# EmgFilterModule.net
KiCad netlist of a schematic drawn in Altium Designer
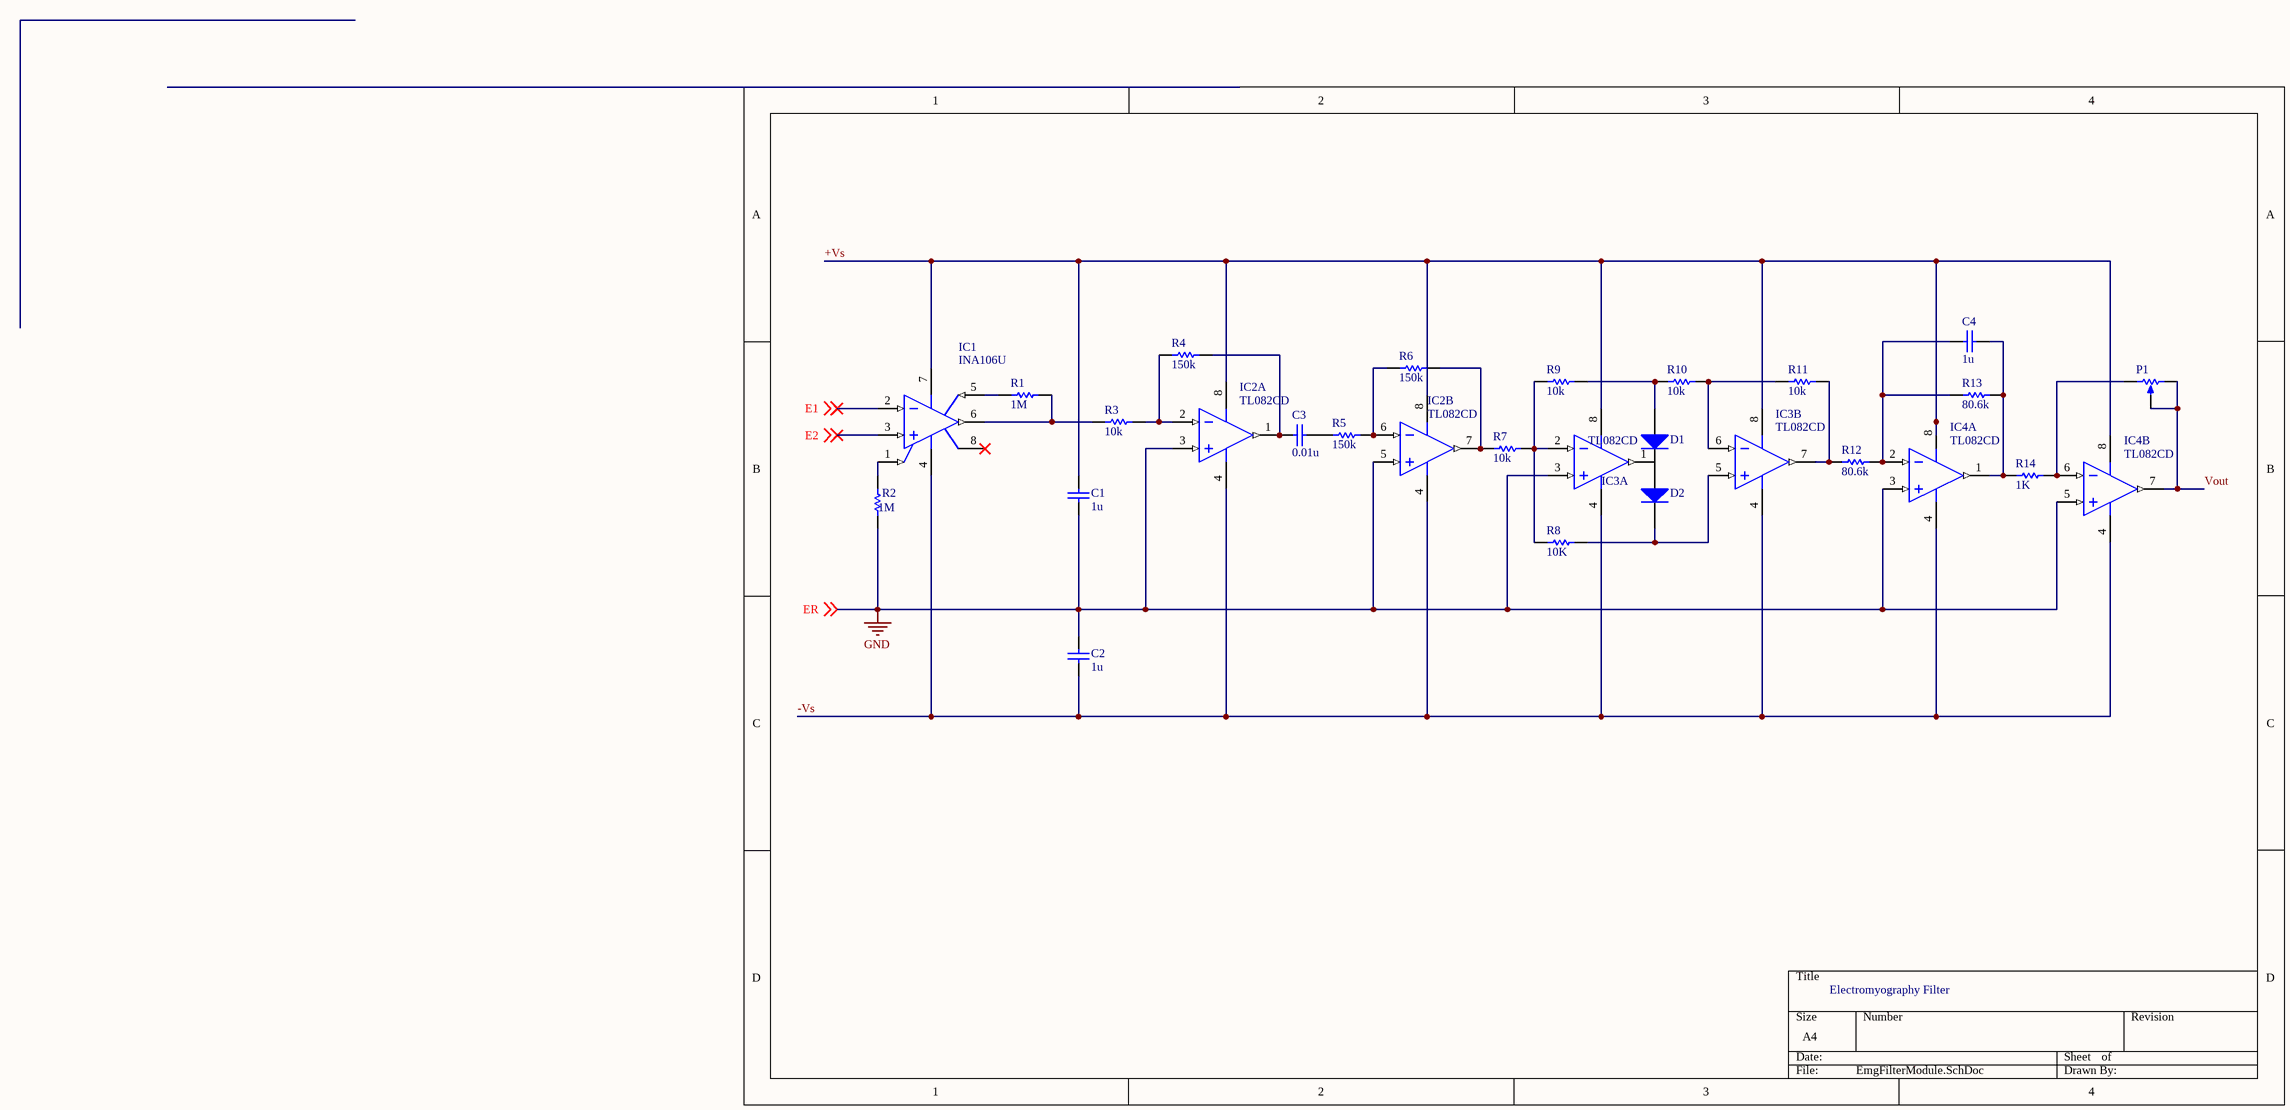
[diagram p0: EmgFilterModule.SchDoc]

(export (version "E")
  (design (tool "Eeschema 10.0.6"))
  (components
    (comp (ref "C1")
      (value "1u")
      (description "Capacitor")
      (libsource (lib "Simulation Generic Components") (part "Capacitor"))
    )
    (comp (ref "C2")
      (value "1u")
      (description "Capacitor")
      (libsource (lib "Simulation Generic Components") (part "Capacitor"))
    )
    (comp (ref "C3")
      (value "0.01u")
      (description "Capacitor")
      (libsource (lib "Simulation Generic Components") (part "Capacitor"))
    )
    (comp (ref "C4")
      (value "1u")
      (description "Capacitor")
      (libsource (lib "Simulation Generic Components") (part "Capacitor"))
    )
    (comp (ref "D1") (value "Diode") (libsource (lib "Simulation Generic Components") (part "Diode")))
    (comp (ref "D2") (value "Diode") (libsource (lib "Simulation Generic Components") (part "Diode")))
    (comp (ref "IC1")
      (value "INA106U")
      (footprint "D0008A_M")
      (fields (field (name "MANUFACTURER") "Texas Instruments"))
      (libsource (lib "Altium Content Vault") (part "TI-INA1XXXX8"))
    )
    (comp (ref "IC2")
      (value "TL082CD")
      (footprint "D0008A_L")
      (fields (field (name "MANUFACTURER") "Texas Instruments"))
      (libsource (lib "Altium Content Vault") (part "TI-AMP-D6-2-8_D"))
    )
    (comp (ref "IC3")
      (value "TL082CD")
      (footprint "D0008A_L")
      (fields (field (name "MANUFACTURER") "Texas Instruments"))
      (libsource (lib "Altium Content Vault") (part "TI-AMP-D6-2-8_D"))
    )
    (comp (ref "IC4")
      (value "TL082CD")
      (footprint "D0008A_L")
      (fields (field (name "MANUFACTURER") "Texas Instruments"))
      (libsource (lib "Altium Content Vault") (part "TI-AMP-D6-2-8_D"))
    )
    (comp (ref "P1")
      (value "Potentiometer")
      (libsource (lib "Simulation Generic Components") (part "Potentiometer"))
    )
    (comp (ref "R1")
      (value "1M")
      (description "Resistor")
      (libsource (lib "Simulation Generic Components") (part "Resistor"))
    )
    (comp (ref "R2")
      (value "1M")
      (description "Resistor")
      (libsource (lib "Simulation Generic Components") (part "Resistor"))
    )
    (comp (ref "R3")
      (value "10k")
      (description "Resistor")
      (libsource (lib "Simulation Generic Components") (part "Resistor"))
    )
    (comp (ref "R4")
      (value "150k")
      (description "Resistor")
      (libsource (lib "Simulation Generic Components") (part "Resistor"))
    )
    (comp (ref "R5")
      (value "150k")
      (description "Resistor")
      (libsource (lib "Simulation Generic Components") (part "Resistor"))
    )
    (comp (ref "R6")
      (value "150k")
      (description "Resistor")
      (libsource (lib "Simulation Generic Components") (part "Resistor"))
    )
    (comp (ref "R7")
      (value "10k")
      (description "Resistor")
      (libsource (lib "Simulation Generic Components") (part "Resistor"))
    )
    (comp (ref "R8")
      (value "10K")
      (description "Resistor")
      (libsource (lib "Simulation Generic Components") (part "Resistor"))
    )
    (comp (ref "R9")
      (value "10k")
      (description "Resistor")
      (libsource (lib "Simulation Generic Components") (part "Resistor"))
    )
    (comp (ref "R10")
      (value "10k")
      (description "Resistor")
      (libsource (lib "Simulation Generic Components") (part "Resistor"))
    )
    (comp (ref "R11")
      (value "10k")
      (description "Resistor")
      (libsource (lib "Simulation Generic Components") (part "Resistor"))
    )
    (comp (ref "R12")
      (value "80.6k")
      (description "Resistor")
      (libsource (lib "Simulation Generic Components") (part "Resistor"))
    )
    (comp (ref "R13")
      (value "80.6k")
      (description "Resistor")
      (libsource (lib "Simulation Generic Components") (part "Resistor"))
    )
    (comp (ref "R14")
      (value "1K")
      (description "Resistor")
      (libsource (lib "Simulation Generic Components") (part "Resistor"))
    )
  )
  (nets
    (net (code "1") (name "/+Vs") (class "Default")
      (node (ref "C1") (pin "2") (pinfunction "2_2") (pintype "passive"))
      (node (ref "IC1") (pin "7") (pinfunction "V+_7") (pintype "power_in"))
      (node (ref "IC2") (pin "8") (pinfunction "VCC+_8") (pintype "power_in"))
      (node (ref "IC3") (pin "8") (pinfunction "VCC+_8") (pintype "power_in"))
      (node (ref "IC4") (pin "8") (pinfunction "VCC+_8") (pintype "power_in"))
    )
    (net (code "2") (name "/-Vs") (class "Default")
      (node (ref "C2") (pin "1") (pinfunction "1_1") (pintype "passive"))
      (node (ref "IC1") (pin "4") (pinfunction "V-_4") (pintype "power_in"))
      (node (ref "IC2") (pin "4") (pinfunction "VCC-_4") (pintype "power_in"))
      (node (ref "IC3") (pin "4") (pinfunction "VCC-_4") (pintype "power_in"))
      (node (ref "IC4") (pin "4") (pinfunction "VCC-_4") (pintype "power_in"))
    )
    (net (code "3") (name "/Vout") (class "Default")
      (node (ref "IC4") (pin "7") (pinfunction "OUT2_7") (pintype "output"))
      (node (ref "P1") (pin "2") (pinfunction "BOT_2") (pintype "passive"))
      (node (ref "P1") (pin "3") (pinfunction "TAP_3") (pintype "passive"))
    )
    (net (code "4") (name "E1") (class "Default")
      (node (ref "IC1") (pin "2") (pinfunction "IN-_2") (pintype "input"))
    )
    (net (code "5") (name "E2") (class "Default")
      (node (ref "IC1") (pin "3") (pinfunction "IN+_3") (pintype "input"))
    )
    (net (code "6") (name "ER") (class "Default")
      (node (ref "C1") (pin "1") (pinfunction "1_1") (pintype "passive"))
      (node (ref "C2") (pin "2") (pinfunction "2_2") (pintype "passive"))
      (node (ref "IC2") (pin "3") (pinfunction "IN1+_3") (pintype "input"))
      (node (ref "IC2") (pin "5") (pinfunction "IN2+_5") (pintype "input"))
      (node (ref "IC3") (pin "3") (pinfunction "IN1+_3") (pintype "input"))
      (node (ref "IC4") (pin "3") (pinfunction "IN1+_3") (pintype "input"))
      (node (ref "IC4") (pin "5") (pinfunction "IN2+_5") (pintype "input"))
      (node (ref "R2") (pin "1") (pinfunction "1_1") (pintype "passive"))
    )
    (net (code "7") (name "Net-(C3-Pad2)") (class "Default")
      (node (ref "C3") (pin "2") (pinfunction "2_2") (pintype "passive"))
      (node (ref "R5") (pin "1") (pinfunction "1_1") (pintype "passive"))
    )
    (net (code "8") (name "Net-(D1-A)") (class "Default")
      (node (ref "D1") (pin "1") (pinfunction "A_1") (pintype "passive"))
      (node (ref "R10") (pin "1") (pinfunction "1_1") (pintype "passive"))
      (node (ref "R9") (pin "2") (pinfunction "2_2") (pintype "passive"))
    )
    (net (code "9") (name "Net-(D2-A)") (class "Default")
      (node (ref "D2") (pin "1") (pinfunction "A_1") (pintype "passive"))
      (node (ref "IC3") (pin "1") (pinfunction "OUT1_1") (pintype "output"))
    )
    (net (code "10") (name "Net-(D2-K)") (class "Default")
      (node (ref "D2") (pin "2") (pinfunction "K_2") (pintype "passive"))
      (node (ref "IC3") (pin "5") (pinfunction "IN2+_5") (pintype "input"))
      (node (ref "R8") (pin "2") (pinfunction "2_2") (pintype "passive"))
    )
    (net (code "11") (name "Net-(IC1-OUT)") (class "Default")
      (node (ref "IC1") (pin "6") (pinfunction "OUT_6") (pintype "output"))
      (node (ref "R1") (pin "2") (pinfunction "2_2") (pintype "passive"))
      (node (ref "R3") (pin "1") (pinfunction "1_1") (pintype "passive"))
    )
    (net (code "12") (name "Net-(IC1-REF)") (class "Default")
      (node (ref "IC1") (pin "1") (pinfunction "REF_1") (pintype "input"))
      (node (ref "R2") (pin "2") (pinfunction "2_2") (pintype "passive"))
    )
    (net (code "13") (name "Net-(IC1-SENSE)") (class "Default")
      (node (ref "IC1") (pin "5") (pinfunction "SENSE_5") (pintype "input"))
      (node (ref "R1") (pin "1") (pinfunction "1_1") (pintype "passive"))
    )
    (net (code "14") (name "Net-(IC2A-IN1-)") (class "Default")
      (node (ref "IC2") (pin "2") (pinfunction "IN1-_2") (pintype "input"))
      (node (ref "R3") (pin "2") (pinfunction "2_2") (pintype "passive"))
      (node (ref "R4") (pin "1") (pinfunction "1_1") (pintype "passive"))
    )
    (net (code "15") (name "Net-(IC2A-OUT1)") (class "Default")
      (node (ref "C3") (pin "1") (pinfunction "1_1") (pintype "passive"))
      (node (ref "IC2") (pin "1") (pinfunction "OUT1_1") (pintype "output"))
      (node (ref "R4") (pin "2") (pinfunction "2_2") (pintype "passive"))
    )
    (net (code "16") (name "Net-(IC2B-IN2-)") (class "Default")
      (node (ref "IC2") (pin "6") (pinfunction "IN2-_6") (pintype "input"))
      (node (ref "R5") (pin "2") (pinfunction "2_2") (pintype "passive"))
      (node (ref "R6") (pin "1") (pinfunction "1_1") (pintype "passive"))
    )
    (net (code "17") (name "Net-(IC2B-OUT2)") (class "Default")
      (node (ref "IC2") (pin "7") (pinfunction "OUT2_7") (pintype "output"))
      (node (ref "R6") (pin "2") (pinfunction "2_2") (pintype "passive"))
      (node (ref "R7") (pin "1") (pinfunction "1_1") (pintype "passive"))
    )
    (net (code "18") (name "Net-(IC3A-IN1-)") (class "Default")
      (node (ref "IC3") (pin "2") (pinfunction "IN1-_2") (pintype "input"))
      (node (ref "R7") (pin "2") (pinfunction "2_2") (pintype "passive"))
      (node (ref "R8") (pin "1") (pinfunction "1_1") (pintype "passive"))
      (node (ref "R9") (pin "1") (pinfunction "1_1") (pintype "passive"))
    )
    (net (code "19") (name "Net-(IC3B-IN2-)") (class "Default")
      (node (ref "IC3") (pin "6") (pinfunction "IN2-_6") (pintype "input"))
      (node (ref "R10") (pin "2") (pinfunction "2_2") (pintype "passive"))
      (node (ref "R11") (pin "1") (pinfunction "1_1") (pintype "passive"))
    )
    (net (code "20") (name "Net-(IC3B-OUT2)") (class "Default")
      (node (ref "IC3") (pin "7") (pinfunction "OUT2_7") (pintype "output"))
      (node (ref "R11") (pin "2") (pinfunction "2_2") (pintype "passive"))
      (node (ref "R12") (pin "1") (pinfunction "1_1") (pintype "passive"))
    )
    (net (code "21") (name "Net-(IC4A-IN1-)") (class "Default")
      (node (ref "C4") (pin "1") (pinfunction "1_1") (pintype "passive"))
      (node (ref "IC4") (pin "2") (pinfunction "IN1-_2") (pintype "input"))
      (node (ref "R12") (pin "2") (pinfunction "2_2") (pintype "passive"))
      (node (ref "R13") (pin "1") (pinfunction "1_1") (pintype "passive"))
    )
    (net (code "22") (name "Net-(IC4A-OUT1)") (class "Default")
      (node (ref "C4") (pin "2") (pinfunction "2_2") (pintype "passive"))
      (node (ref "IC4") (pin "1") (pinfunction "OUT1_1") (pintype "output"))
      (node (ref "R13") (pin "2") (pinfunction "2_2") (pintype "passive"))
      (node (ref "R14") (pin "1") (pinfunction "1_1") (pintype "passive"))
    )
    (net (code "23") (name "Net-(IC4B-IN2-)") (class "Default")
      (node (ref "IC4") (pin "6") (pinfunction "IN2-_6") (pintype "input"))
      (node (ref "P1") (pin "1") (pinfunction "TOP_1") (pintype "passive"))
      (node (ref "R14") (pin "2") (pinfunction "2_2") (pintype "passive"))
    )
    (net (code "24") (name "unconnected-(D1-K-Pad2)") (class "Default")
      (node (ref "D1") (pin "2") (pinfunction "K_2") (pintype "passive"))
    )
    (net (code "25") (name "unconnected-(IC1-NC-Pad8)") (class "Default")
      (node (ref "IC1") (pin "8") (pinfunction "NC_8") (pintype "passive+no_connect"))
    )
  )
)
